# moottoriohjain.net
KiCad netlist of a schematic drawn in EAGLE
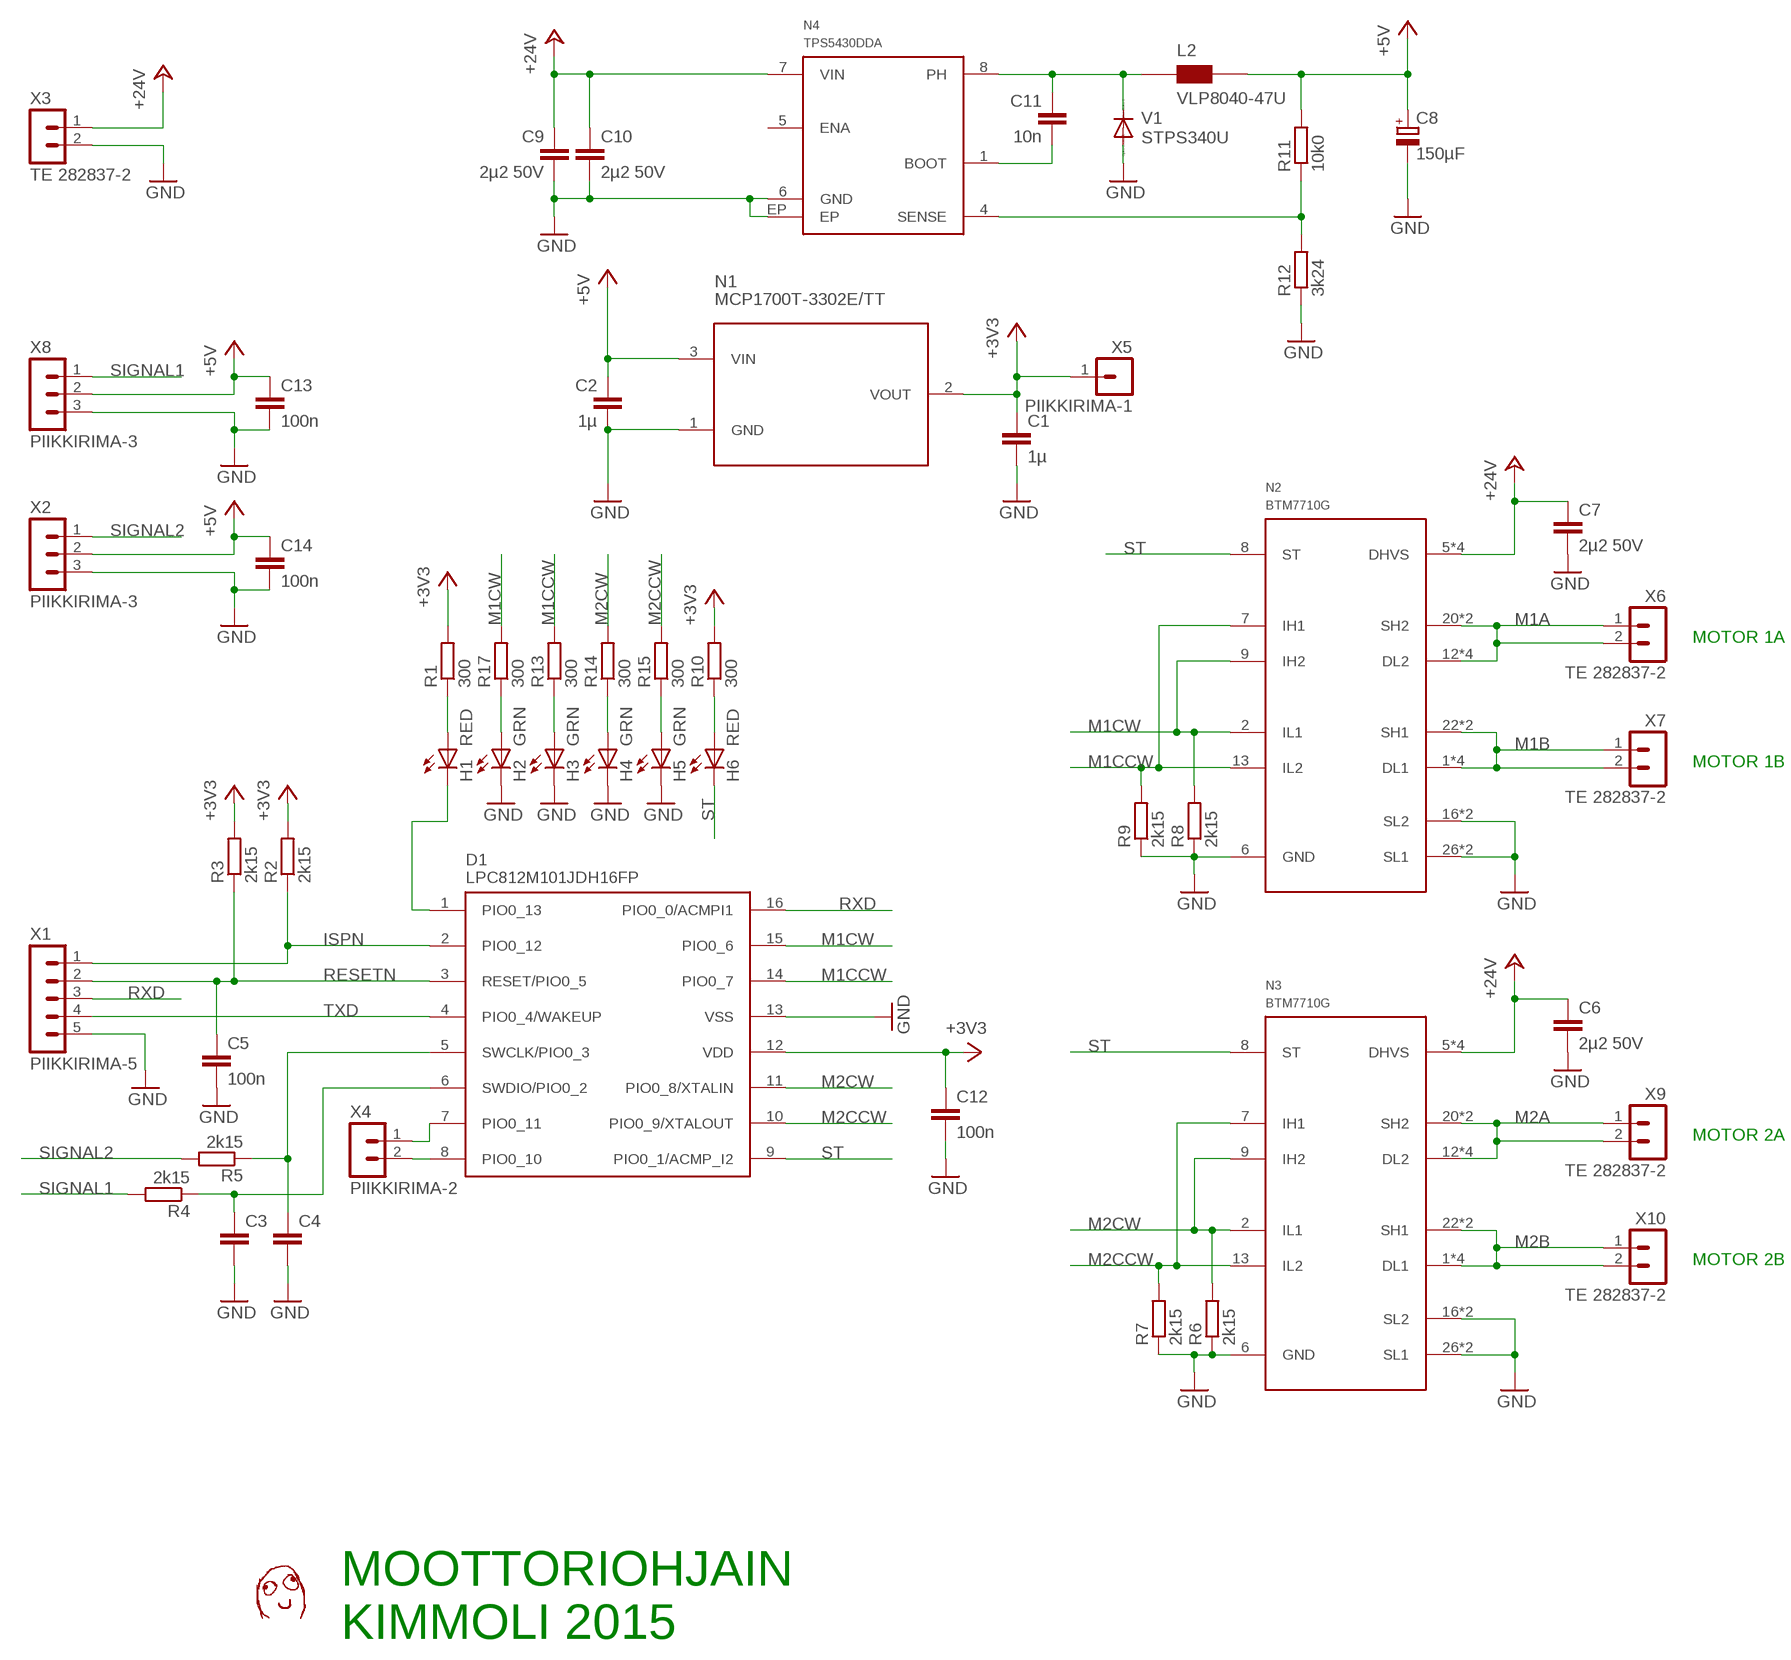
[diagram p0: schematic, sheet 1]

(export (version "E")
  (design (tool "Eeschema 10.0.6"))
  (components
    (comp (ref "C1")
      (value "1µ")
      (footprint "eagle-import:C0805")
      (libsource (lib "eagle-import") (part "omat_ic_2_CAP0805"))
    )
    (comp (ref "C2")
      (value "1µ")
      (footprint "eagle-import:C0805")
      (libsource (lib "eagle-import") (part "omat_ic_2_CAP0805"))
    )
    (comp (ref "C3")
      (value "CAP0603")
      (footprint "eagle-import:C0603")
      (libsource (lib "eagle-import") (part "omat_ic_2_CAP0603"))
    )
    (comp (ref "C4")
      (value "CAP0603")
      (footprint "eagle-import:C0603")
      (libsource (lib "eagle-import") (part "omat_ic_2_CAP0603"))
    )
    (comp (ref "C5")
      (value "100n")
      (footprint "eagle-import:C0603")
      (libsource (lib "eagle-import") (part "omat_ic_2_CAP0603"))
    )
    (comp (ref "C6")
      (value "2µ2 50V")
      (footprint "eagle-import:C0805")
      (libsource (lib "eagle-import") (part "CAP0805"))
    )
    (comp (ref "C7")
      (value "2µ2 50V")
      (footprint "eagle-import:C0805")
      (libsource (lib "eagle-import") (part "CAP0805"))
    )
    (comp (ref "C8")
      (value "150µF")
      (footprint "eagle-import:CT7343")
      (libsource (lib "eagle-import") (part "CPOL-EUCT7343"))
    )
    (comp (ref "C9")
      (value "2µ2 50V")
      (footprint "eagle-import:C0805")
      (libsource (lib "eagle-import") (part "CAP0805"))
    )
    (comp (ref "C10")
      (value "2µ2 50V")
      (footprint "eagle-import:C0805")
      (libsource (lib "eagle-import") (part "CAP0805"))
    )
    (comp (ref "C11")
      (value "10n")
      (footprint "eagle-import:C0603")
      (libsource (lib "eagle-import") (part "omat_ic_2_CAP0603"))
    )
    (comp (ref "C12")
      (value "100n")
      (footprint "eagle-import:C0603")
      (libsource (lib "eagle-import") (part "omat_ic_2_CAP0603"))
    )
    (comp (ref "C13")
      (value "100n")
      (footprint "eagle-import:C0603")
      (libsource (lib "eagle-import") (part "omat_ic_2_CAP0603"))
    )
    (comp (ref "C14")
      (value "100n")
      (footprint "eagle-import:C0603")
      (libsource (lib "eagle-import") (part "omat_ic_2_CAP0603"))
    )
    (comp (ref "D1")
      (value "LPC812M101JDH16FP")
      (footprint "eagle-import:SEB_TSSOP16")
      (libsource (lib "eagle-import") (part "SEB_LPC81X"))
    )
    (comp (ref "H1")
      (value "RED")
      (footprint "eagle-import:CHIP-LED0603")
      (libsource (lib "eagle-import") (part "LEDCHIP-LED0603"))
    )
    (comp (ref "H2")
      (value "GRN")
      (footprint "eagle-import:CHIP-LED0603")
      (libsource (lib "eagle-import") (part "LEDCHIP-LED0603"))
    )
    (comp (ref "H3")
      (value "GRN")
      (footprint "eagle-import:CHIP-LED0603")
      (libsource (lib "eagle-import") (part "LEDCHIP-LED0603"))
    )
    (comp (ref "H4")
      (value "GRN")
      (footprint "eagle-import:CHIP-LED0603")
      (libsource (lib "eagle-import") (part "LEDCHIP-LED0603"))
    )
    (comp (ref "H5")
      (value "GRN")
      (footprint "eagle-import:CHIP-LED0603")
      (libsource (lib "eagle-import") (part "LEDCHIP-LED0603"))
    )
    (comp (ref "H6")
      (value "RED")
      (footprint "eagle-import:CHIP-LED0603")
      (libsource (lib "eagle-import") (part "LEDCHIP-LED0603"))
    )
    (comp (ref "L2")
      (value "VLP8040-47U")
      (footprint "eagle-import:VLP8040")
      (libsource (lib "eagle-import") (part "VLP8040-47U"))
    )
    (comp (ref "N1")
      (value "MCP1700T-3302E/TT")
      (footprint "eagle-import:SOT23")
      (libsource (lib "eagle-import") (part "MCP1700T-1802E/TT"))
    )
    (comp (ref "N2")
      (value "BTM7710G")
      (footprint "eagle-import:SOIC28-W_MC")
      (libsource (lib "eagle-import") (part "BTM7710G"))
    )
    (comp (ref "N3")
      (value "BTM7710G")
      (footprint "eagle-import:SOIC28-W_MC")
      (libsource (lib "eagle-import") (part "BTM7710G"))
    )
    (comp (ref "N4")
      (value "TPS5430DDA")
      (footprint "eagle-import:SOIC8-N-EP")
      (libsource (lib "eagle-import") (part "TPS5430DDA"))
    )
    (comp (ref "R1")
      (value "300")
      (footprint "eagle-import:R0603")
      (libsource (lib "eagle-import") (part "omat_ic_2_RES0603"))
    )
    (comp (ref "R2")
      (value "2k15")
      (footprint "eagle-import:R0603")
      (libsource (lib "eagle-import") (part "omat_ic_2_RES0603"))
    )
    (comp (ref "R3")
      (value "2k15")
      (footprint "eagle-import:R0603")
      (libsource (lib "eagle-import") (part "omat_ic_2_RES0603"))
    )
    (comp (ref "R4")
      (value "2k15")
      (footprint "eagle-import:R0603")
      (libsource (lib "eagle-import") (part "omat_ic_2_RES0603"))
    )
    (comp (ref "R5")
      (value "2k15")
      (footprint "eagle-import:R0603")
      (libsource (lib "eagle-import") (part "omat_ic_2_RES0603"))
    )
    (comp (ref "R6")
      (value "2k15")
      (footprint "eagle-import:R0603")
      (libsource (lib "eagle-import") (part "omat_ic_2_RES0603"))
    )
    (comp (ref "R7")
      (value "2k15")
      (footprint "eagle-import:R0603")
      (libsource (lib "eagle-import") (part "omat_ic_2_RES0603"))
    )
    (comp (ref "R8")
      (value "2k15")
      (footprint "eagle-import:R0603")
      (libsource (lib "eagle-import") (part "omat_ic_2_RES0603"))
    )
    (comp (ref "R9")
      (value "2k15")
      (footprint "eagle-import:R0603")
      (libsource (lib "eagle-import") (part "omat_ic_2_RES0603"))
    )
    (comp (ref "R10")
      (value "300")
      (footprint "eagle-import:R0603")
      (libsource (lib "eagle-import") (part "omat_ic_2_RES0603"))
    )
    (comp (ref "R11")
      (value "10k0")
      (footprint "eagle-import:R0603")
      (libsource (lib "eagle-import") (part "RES0603"))
    )
    (comp (ref "R12")
      (value "3k24")
      (footprint "eagle-import:R0603")
      (libsource (lib "eagle-import") (part "RES0603"))
    )
    (comp (ref "R13")
      (value "300")
      (footprint "eagle-import:R0603")
      (libsource (lib "eagle-import") (part "omat_ic_2_RES0603"))
    )
    (comp (ref "R14")
      (value "300")
      (footprint "eagle-import:R0603")
      (libsource (lib "eagle-import") (part "omat_ic_2_RES0603"))
    )
    (comp (ref "R15")
      (value "300")
      (footprint "eagle-import:R0603")
      (libsource (lib "eagle-import") (part "omat_ic_2_RES0603"))
    )
    (comp (ref "R17")
      (value "300")
      (footprint "eagle-import:R0603")
      (libsource (lib "eagle-import") (part "omat_ic_2_RES0603"))
    )
    (comp (ref "U$1")
      (value "DAFUG")
      (footprint "eagle-import:DAFUG")
      (libsource (lib "eagle-import") (part "DAFUG"))
    )
    (comp (ref "V1")
      (value "STPS340U")
      (footprint "eagle-import:SMB")
      (libsource (lib "eagle-import") (part "DIODE-SMB"))
    )
    (comp (ref "X1")
      (value "PIIKKIRIMA-5")
      (footprint "eagle-import:PIIKKIRIMA-5")
      (libsource (lib "eagle-import") (part "PIIKKIRIMA-5"))
    )
    (comp (ref "X2")
      (value "PIIKKIRIMA-3")
      (footprint "eagle-import:PIIKKIRIMA-3")
      (libsource (lib "eagle-import") (part "PIIKKIRIMA-3"))
    )
    (comp (ref "X3")
      (value "TE 282837-2")
      (footprint "eagle-import:TE_RUUVILIITIN2")
      (libsource (lib "eagle-import") (part "TE_RUUVILIITIN2"))
    )
    (comp (ref "X4")
      (value "PIIKKIRIMA-2")
      (footprint "eagle-import:PIIKKIRIMA-2")
      (libsource (lib "eagle-import") (part "PIIKKIRIMA-2"))
    )
    (comp (ref "X5")
      (value "PIIKKIRIMA-1")
      (footprint "eagle-import:PIIKKIRIMA-1")
      (libsource (lib "eagle-import") (part "PIIKKIRIMA-1"))
    )
    (comp (ref "X6")
      (value "TE 282837-2")
      (footprint "eagle-import:TE_RUUVILIITIN2")
      (libsource (lib "eagle-import") (part "TE_RUUVILIITIN2"))
    )
    (comp (ref "X7")
      (value "TE 282837-2")
      (footprint "eagle-import:TE_RUUVILIITIN2")
      (libsource (lib "eagle-import") (part "TE_RUUVILIITIN2"))
    )
    (comp (ref "X8")
      (value "PIIKKIRIMA-3")
      (footprint "eagle-import:PIIKKIRIMA-3")
      (libsource (lib "eagle-import") (part "PIIKKIRIMA-3"))
    )
    (comp (ref "X9")
      (value "TE 282837-2")
      (footprint "eagle-import:TE_RUUVILIITIN2")
      (libsource (lib "eagle-import") (part "TE_RUUVILIITIN2"))
    )
    (comp (ref "X10")
      (value "TE 282837-2")
      (footprint "eagle-import:TE_RUUVILIITIN2")
      (libsource (lib "eagle-import") (part "TE_RUUVILIITIN2"))
    )
  )
  (nets
    (net (code "1") (name "+3V3") (class "Default")
      (node (ref "C1") (pin "1") (pinfunction "1_1") (pintype "passive"))
      (node (ref "C12") (pin "1") (pinfunction "1_1") (pintype "passive"))
      (node (ref "D1") (pin "12") (pinfunction "VDD_12") (pintype "bidirectional"))
      (node (ref "N1") (pin "2") (pinfunction "VOUT_2") (pintype "bidirectional"))
      (node (ref "R1") (pin "2") (pinfunction "2_2") (pintype "passive"))
      (node (ref "R10") (pin "2") (pinfunction "2_2") (pintype "passive"))
      (node (ref "R2") (pin "2") (pinfunction "2_2") (pintype "passive"))
      (node (ref "R3") (pin "2") (pinfunction "2_2") (pintype "passive"))
      (node (ref "X5") (pin "1") (pinfunction "1_1") (pintype "passive"))
    )
    (net (code "2") (name "+5V") (class "Default")
      (node (ref "C13") (pin "1") (pinfunction "1_1") (pintype "passive"))
      (node (ref "C14") (pin "1") (pinfunction "1_1") (pintype "passive"))
      (node (ref "C2") (pin "1") (pinfunction "1_1") (pintype "passive"))
      (node (ref "C8") (pin "+") (pinfunction "+_+") (pintype "passive"))
      (node (ref "L2") (pin "2") (pinfunction "B_2") (pintype "bidirectional"))
      (node (ref "N1") (pin "3") (pinfunction "VIN_3") (pintype "bidirectional"))
      (node (ref "R11") (pin "2") (pinfunction "2_2") (pintype "passive"))
      (node (ref "X2") (pin "2") (pinfunction "2_2") (pintype "passive"))
      (node (ref "X8") (pin "2") (pinfunction "2_2") (pintype "passive"))
    )
    (net (code "3") (name "+24V") (class "Default")
      (node (ref "C10") (pin "1") (pinfunction "1_1") (pintype "passive"))
      (node (ref "C6") (pin "1") (pinfunction "1_1") (pintype "passive"))
      (node (ref "C7") (pin "1") (pinfunction "1_1") (pintype "passive"))
      (node (ref "C9") (pin "1") (pinfunction "1_1") (pintype "passive"))
      (node (ref "N2") (pin "10") (pinfunction "DHVS_10") (pintype "bidirectional"))
      (node (ref "N2") (pin "19") (pinfunction "DHVS_19") (pintype "bidirectional"))
      (node (ref "N2") (pin "24") (pinfunction "DHVS_24") (pintype "bidirectional"))
      (node (ref "N2") (pin "5") (pinfunction "DHVS_5") (pintype "bidirectional"))
      (node (ref "N3") (pin "10") (pinfunction "DHVS_10") (pintype "bidirectional"))
      (node (ref "N3") (pin "19") (pinfunction "DHVS_19") (pintype "bidirectional"))
      (node (ref "N3") (pin "24") (pinfunction "DHVS_24") (pintype "bidirectional"))
      (node (ref "N3") (pin "5") (pinfunction "DHVS_5") (pintype "bidirectional"))
      (node (ref "N4") (pin "7") (pinfunction "VIN_7") (pintype "bidirectional"))
      (node (ref "X3") (pin "1") (pinfunction "1_1") (pintype "passive"))
    )
    (net (code "4") (name "/ISPN") (class "Default")
      (node (ref "D1") (pin "2") (pinfunction "PIO0_12_2") (pintype "bidirectional"))
      (node (ref "R2") (pin "1") (pinfunction "1_1") (pintype "passive"))
      (node (ref "X1") (pin "1") (pinfunction "1_1") (pintype "passive"))
    )
    (net (code "5") (name "/M1A") (class "Default")
      (node (ref "N2") (pin "12") (pinfunction "DL2_12") (pintype "bidirectional"))
      (node (ref "N2") (pin "14") (pinfunction "DL2_14") (pintype "bidirectional"))
      (node (ref "N2") (pin "15") (pinfunction "DL2_15") (pintype "bidirectional"))
      (node (ref "N2") (pin "18") (pinfunction "DL2_18") (pintype "bidirectional"))
      (node (ref "N2") (pin "20") (pinfunction "SH2_20") (pintype "bidirectional"))
      (node (ref "N2") (pin "21") (pinfunction "SH2_21") (pintype "bidirectional"))
      (node (ref "X6") (pin "1") (pinfunction "1_1") (pintype "passive"))
      (node (ref "X6") (pin "2") (pinfunction "2_2") (pintype "passive"))
    )
    (net (code "6") (name "/M1B") (class "Default")
      (node (ref "N2") (pin "1") (pinfunction "DL1_1") (pintype "bidirectional"))
      (node (ref "N2") (pin "22") (pinfunction "SH1_22") (pintype "bidirectional"))
      (node (ref "N2") (pin "23") (pinfunction "SH1_23") (pintype "bidirectional"))
      (node (ref "N2") (pin "25") (pinfunction "DL1_25") (pintype "bidirectional"))
      (node (ref "N2") (pin "28") (pinfunction "DL1_28") (pintype "bidirectional"))
      (node (ref "N2") (pin "3") (pinfunction "DL1_3") (pintype "bidirectional"))
      (node (ref "X7") (pin "1") (pinfunction "1_1") (pintype "passive"))
      (node (ref "X7") (pin "2") (pinfunction "2_2") (pintype "passive"))
    )
    (net (code "7") (name "/M1CCW") (class "Default")
      (node (ref "D1") (pin "14") (pinfunction "PIO0_7_14") (pintype "bidirectional"))
      (node (ref "N2") (pin "13") (pinfunction "IL2_13") (pintype "bidirectional"))
      (node (ref "N2") (pin "7") (pinfunction "IH1_7") (pintype "bidirectional"))
      (node (ref "R13") (pin "2") (pinfunction "2_2") (pintype "passive"))
      (node (ref "R9") (pin "2") (pinfunction "2_2") (pintype "passive"))
    )
    (net (code "8") (name "/M1CW") (class "Default")
      (node (ref "D1") (pin "15") (pinfunction "PIO0_6_15") (pintype "bidirectional"))
      (node (ref "N2") (pin "2") (pinfunction "IL1_2") (pintype "bidirectional"))
      (node (ref "N2") (pin "9") (pinfunction "IH2_9") (pintype "bidirectional"))
      (node (ref "R17") (pin "2") (pinfunction "2_2") (pintype "passive"))
      (node (ref "R8") (pin "2") (pinfunction "2_2") (pintype "passive"))
    )
    (net (code "9") (name "/M2A") (class "Default")
      (node (ref "N3") (pin "12") (pinfunction "DL2_12") (pintype "bidirectional"))
      (node (ref "N3") (pin "14") (pinfunction "DL2_14") (pintype "bidirectional"))
      (node (ref "N3") (pin "15") (pinfunction "DL2_15") (pintype "bidirectional"))
      (node (ref "N3") (pin "18") (pinfunction "DL2_18") (pintype "bidirectional"))
      (node (ref "N3") (pin "20") (pinfunction "SH2_20") (pintype "bidirectional"))
      (node (ref "N3") (pin "21") (pinfunction "SH2_21") (pintype "bidirectional"))
      (node (ref "X9") (pin "1") (pinfunction "1_1") (pintype "passive"))
      (node (ref "X9") (pin "2") (pinfunction "2_2") (pintype "passive"))
    )
    (net (code "10") (name "/M2B") (class "Default")
      (node (ref "N3") (pin "1") (pinfunction "DL1_1") (pintype "bidirectional"))
      (node (ref "N3") (pin "22") (pinfunction "SH1_22") (pintype "bidirectional"))
      (node (ref "N3") (pin "23") (pinfunction "SH1_23") (pintype "bidirectional"))
      (node (ref "N3") (pin "25") (pinfunction "DL1_25") (pintype "bidirectional"))
      (node (ref "N3") (pin "28") (pinfunction "DL1_28") (pintype "bidirectional"))
      (node (ref "N3") (pin "3") (pinfunction "DL1_3") (pintype "bidirectional"))
      (node (ref "X10") (pin "1") (pinfunction "1_1") (pintype "passive"))
      (node (ref "X10") (pin "2") (pinfunction "2_2") (pintype "passive"))
    )
    (net (code "11") (name "/M2CCW") (class "Default")
      (node (ref "D1") (pin "10") (pinfunction "PIO0_9/XTALOUT_10") (pintype "bidirectional"))
      (node (ref "N3") (pin "13") (pinfunction "IL2_13") (pintype "bidirectional"))
      (node (ref "N3") (pin "7") (pinfunction "IH1_7") (pintype "bidirectional"))
      (node (ref "R15") (pin "2") (pinfunction "2_2") (pintype "passive"))
      (node (ref "R7") (pin "2") (pinfunction "2_2") (pintype "passive"))
    )
    (net (code "12") (name "/M2CW") (class "Default")
      (node (ref "D1") (pin "11") (pinfunction "PIO0_8/XTALIN_11") (pintype "bidirectional"))
      (node (ref "N3") (pin "2") (pinfunction "IL1_2") (pintype "bidirectional"))
      (node (ref "N3") (pin "9") (pinfunction "IH2_9") (pintype "bidirectional"))
      (node (ref "R14") (pin "2") (pinfunction "2_2") (pintype "passive"))
      (node (ref "R6") (pin "2") (pinfunction "2_2") (pintype "passive"))
    )
    (net (code "13") (name "/RESETN") (class "Default")
      (node (ref "C5") (pin "1") (pinfunction "1_1") (pintype "passive"))
      (node (ref "D1") (pin "3") (pinfunction "RESET/PIO0_5_3") (pintype "bidirectional"))
      (node (ref "R3") (pin "1") (pinfunction "1_1") (pintype "passive"))
      (node (ref "X1") (pin "2") (pinfunction "2_2") (pintype "passive"))
    )
    (net (code "14") (name "/RXD") (class "Default")
      (node (ref "D1") (pin "16") (pinfunction "PIO0_0/ACMPI1_16") (pintype "bidirectional"))
      (node (ref "X1") (pin "3") (pinfunction "3_3") (pintype "passive"))
    )
    (net (code "15") (name "/SIGNAL1") (class "Default")
      (node (ref "R4") (pin "2") (pinfunction "2_2") (pintype "passive"))
      (node (ref "X8") (pin "1") (pinfunction "1_1") (pintype "passive"))
    )
    (net (code "16") (name "/SIGNAL2") (class "Default")
      (node (ref "R5") (pin "2") (pinfunction "2_2") (pintype "passive"))
      (node (ref "X2") (pin "1") (pinfunction "1_1") (pintype "passive"))
    )
    (net (code "17") (name "/ST") (class "Default")
      (node (ref "D1") (pin "9") (pinfunction "PIO0_1/ACMP_I2_9") (pintype "bidirectional"))
      (node (ref "H6") (pin "C") (pinfunction "C_C") (pintype "passive"))
      (node (ref "N2") (pin "8") (pinfunction "ST_8") (pintype "bidirectional"))
      (node (ref "N3") (pin "8") (pinfunction "ST_8") (pintype "bidirectional"))
    )
    (net (code "18") (name "/TXD") (class "Default")
      (node (ref "D1") (pin "4") (pinfunction "PIO0_4/WAKEUP_4") (pintype "bidirectional"))
      (node (ref "X1") (pin "4") (pinfunction "4_4") (pintype "passive"))
    )
    (net (code "19") (name "GND") (class "Default")
      (node (ref "C1") (pin "2") (pinfunction "2_2") (pintype "passive"))
      (node (ref "C10") (pin "2") (pinfunction "2_2") (pintype "passive"))
      (node (ref "C12") (pin "2") (pinfunction "2_2") (pintype "passive"))
      (node (ref "C13") (pin "2") (pinfunction "2_2") (pintype "passive"))
      (node (ref "C14") (pin "2") (pinfunction "2_2") (pintype "passive"))
      (node (ref "C2") (pin "2") (pinfunction "2_2") (pintype "passive"))
      (node (ref "C3") (pin "2") (pinfunction "2_2") (pintype "passive"))
      (node (ref "C4") (pin "2") (pinfunction "2_2") (pintype "passive"))
      (node (ref "C5") (pin "2") (pinfunction "2_2") (pintype "passive"))
      (node (ref "C6") (pin "2") (pinfunction "2_2") (pintype "passive"))
      (node (ref "C7") (pin "2") (pinfunction "2_2") (pintype "passive"))
      (node (ref "C8") (pin "-") (pinfunction "-_-") (pintype "passive"))
      (node (ref "C9") (pin "2") (pinfunction "2_2") (pintype "passive"))
      (node (ref "D1") (pin "13") (pinfunction "VSS_13") (pintype "bidirectional"))
      (node (ref "H2") (pin "C") (pinfunction "C_C") (pintype "passive"))
      (node (ref "H3") (pin "C") (pinfunction "C_C") (pintype "passive"))
      (node (ref "H4") (pin "C") (pinfunction "C_C") (pintype "passive"))
      (node (ref "H5") (pin "C") (pinfunction "C_C") (pintype "passive"))
      (node (ref "N1") (pin "1") (pinfunction "GND_1") (pintype "bidirectional"))
      (node (ref "N2") (pin "16") (pinfunction "SL2_16") (pintype "bidirectional"))
      (node (ref "N2") (pin "17") (pinfunction "SL2_17") (pintype "bidirectional"))
      (node (ref "N2") (pin "26") (pinfunction "SL1_26") (pintype "bidirectional"))
      (node (ref "N2") (pin "27") (pinfunction "SL1_27") (pintype "bidirectional"))
      (node (ref "N2") (pin "6") (pinfunction "GND_6") (pintype "bidirectional"))
      (node (ref "N3") (pin "16") (pinfunction "SL2_16") (pintype "bidirectional"))
      (node (ref "N3") (pin "17") (pinfunction "SL2_17") (pintype "bidirectional"))
      (node (ref "N3") (pin "26") (pinfunction "SL1_26") (pintype "bidirectional"))
      (node (ref "N3") (pin "27") (pinfunction "SL1_27") (pintype "bidirectional"))
      (node (ref "N3") (pin "6") (pinfunction "GND_6") (pintype "bidirectional"))
      (node (ref "N4") (pin "6") (pinfunction "GND_6") (pintype "bidirectional"))
      (node (ref "N4") (pin "EP") (pinfunction "EP_EP") (pintype "bidirectional"))
      (node (ref "R12") (pin "1") (pinfunction "1_1") (pintype "passive"))
      (node (ref "R6") (pin "1") (pinfunction "1_1") (pintype "passive"))
      (node (ref "R7") (pin "1") (pinfunction "1_1") (pintype "passive"))
      (node (ref "R8") (pin "1") (pinfunction "1_1") (pintype "passive"))
      (node (ref "R9") (pin "1") (pinfunction "1_1") (pintype "passive"))
      (node (ref "V1") (pin "A") (pinfunction "A_A") (pintype "passive"))
      (node (ref "X1") (pin "5") (pinfunction "5_5") (pintype "passive"))
      (node (ref "X2") (pin "3") (pinfunction "3_3") (pintype "passive"))
      (node (ref "X3") (pin "2") (pinfunction "2_2") (pintype "passive"))
      (node (ref "X8") (pin "3") (pinfunction "3_3") (pintype "passive"))
    )
    (net (code "20") (name "Net-(D1-PIO0_10)") (class "Default")
      (node (ref "D1") (pin "8") (pinfunction "PIO0_10_8") (pintype "bidirectional"))
      (node (ref "X4") (pin "2") (pinfunction "2_2") (pintype "passive"))
    )
    (net (code "21") (name "Net-(D1-PIO0_11)") (class "Default")
      (node (ref "D1") (pin "7") (pinfunction "PIO0_11_7") (pintype "bidirectional"))
      (node (ref "X4") (pin "1") (pinfunction "1_1") (pintype "passive"))
    )
    (net (code "22") (name "Net-(D1-PIO0_13)") (class "Default")
      (node (ref "D1") (pin "1") (pinfunction "PIO0_13_1") (pintype "bidirectional"))
      (node (ref "H1") (pin "C") (pinfunction "C_C") (pintype "passive"))
    )
    (net (code "23") (name "Net-(D1-SWCLK{slash}PIO0_3)") (class "Default")
      (node (ref "C4") (pin "1") (pinfunction "1_1") (pintype "passive"))
      (node (ref "D1") (pin "5") (pinfunction "SWCLK/PIO0_3_5") (pintype "bidirectional"))
      (node (ref "R5") (pin "1") (pinfunction "1_1") (pintype "passive"))
    )
    (net (code "24") (name "Net-(D1-SWDIO{slash}PIO0_2)") (class "Default")
      (node (ref "C3") (pin "1") (pinfunction "1_1") (pintype "passive"))
      (node (ref "D1") (pin "6") (pinfunction "SWDIO/PIO0_2_6") (pintype "bidirectional"))
      (node (ref "R4") (pin "1") (pinfunction "1_1") (pintype "passive"))
    )
    (net (code "25") (name "Net-(H1-PadA)") (class "Default")
      (node (ref "H1") (pin "A") (pinfunction "A_A") (pintype "passive"))
      (node (ref "R1") (pin "1") (pinfunction "1_1") (pintype "passive"))
    )
    (net (code "26") (name "Net-(H2-PadA)") (class "Default")
      (node (ref "H2") (pin "A") (pinfunction "A_A") (pintype "passive"))
      (node (ref "R17") (pin "1") (pinfunction "1_1") (pintype "passive"))
    )
    (net (code "27") (name "Net-(H3-PadA)") (class "Default")
      (node (ref "H3") (pin "A") (pinfunction "A_A") (pintype "passive"))
      (node (ref "R13") (pin "1") (pinfunction "1_1") (pintype "passive"))
    )
    (net (code "28") (name "Net-(H4-PadA)") (class "Default")
      (node (ref "H4") (pin "A") (pinfunction "A_A") (pintype "passive"))
      (node (ref "R14") (pin "1") (pinfunction "1_1") (pintype "passive"))
    )
    (net (code "29") (name "Net-(H5-PadA)") (class "Default")
      (node (ref "H5") (pin "A") (pinfunction "A_A") (pintype "passive"))
      (node (ref "R15") (pin "1") (pinfunction "1_1") (pintype "passive"))
    )
    (net (code "30") (name "Net-(H6-PadA)") (class "Default")
      (node (ref "H6") (pin "A") (pinfunction "A_A") (pintype "passive"))
      (node (ref "R10") (pin "1") (pinfunction "1_1") (pintype "passive"))
    )
    (net (code "31") (name "Net-(L2-A)") (class "Default")
      (node (ref "C11") (pin "1") (pinfunction "1_1") (pintype "passive"))
      (node (ref "L2") (pin "1") (pinfunction "A_1") (pintype "bidirectional"))
      (node (ref "N4") (pin "8") (pinfunction "PH_8") (pintype "bidirectional"))
      (node (ref "V1") (pin "C") (pinfunction "C_C") (pintype "passive"))
    )
    (net (code "32") (name "Net-(N4-BOOT)") (class "Default")
      (node (ref "C11") (pin "2") (pinfunction "2_2") (pintype "passive"))
      (node (ref "N4") (pin "1") (pinfunction "BOOT_1") (pintype "bidirectional"))
    )
    (net (code "33") (name "Net-(N4-SENSE)") (class "Default")
      (node (ref "N4") (pin "4") (pinfunction "SENSE_4") (pintype "bidirectional"))
      (node (ref "R11") (pin "1") (pinfunction "1_1") (pintype "passive"))
      (node (ref "R12") (pin "2") (pinfunction "2_2") (pintype "passive"))
    )
    (net (code "34") (name "unconnected-(N4-ENA-Pad5)") (class "Default")
      (node (ref "N4") (pin "5") (pinfunction "ENA_5") (pintype "bidirectional"))
    )
  )
)
